# Toplevel.net
KiCad netlist of a schematic drawn in Altium Designer
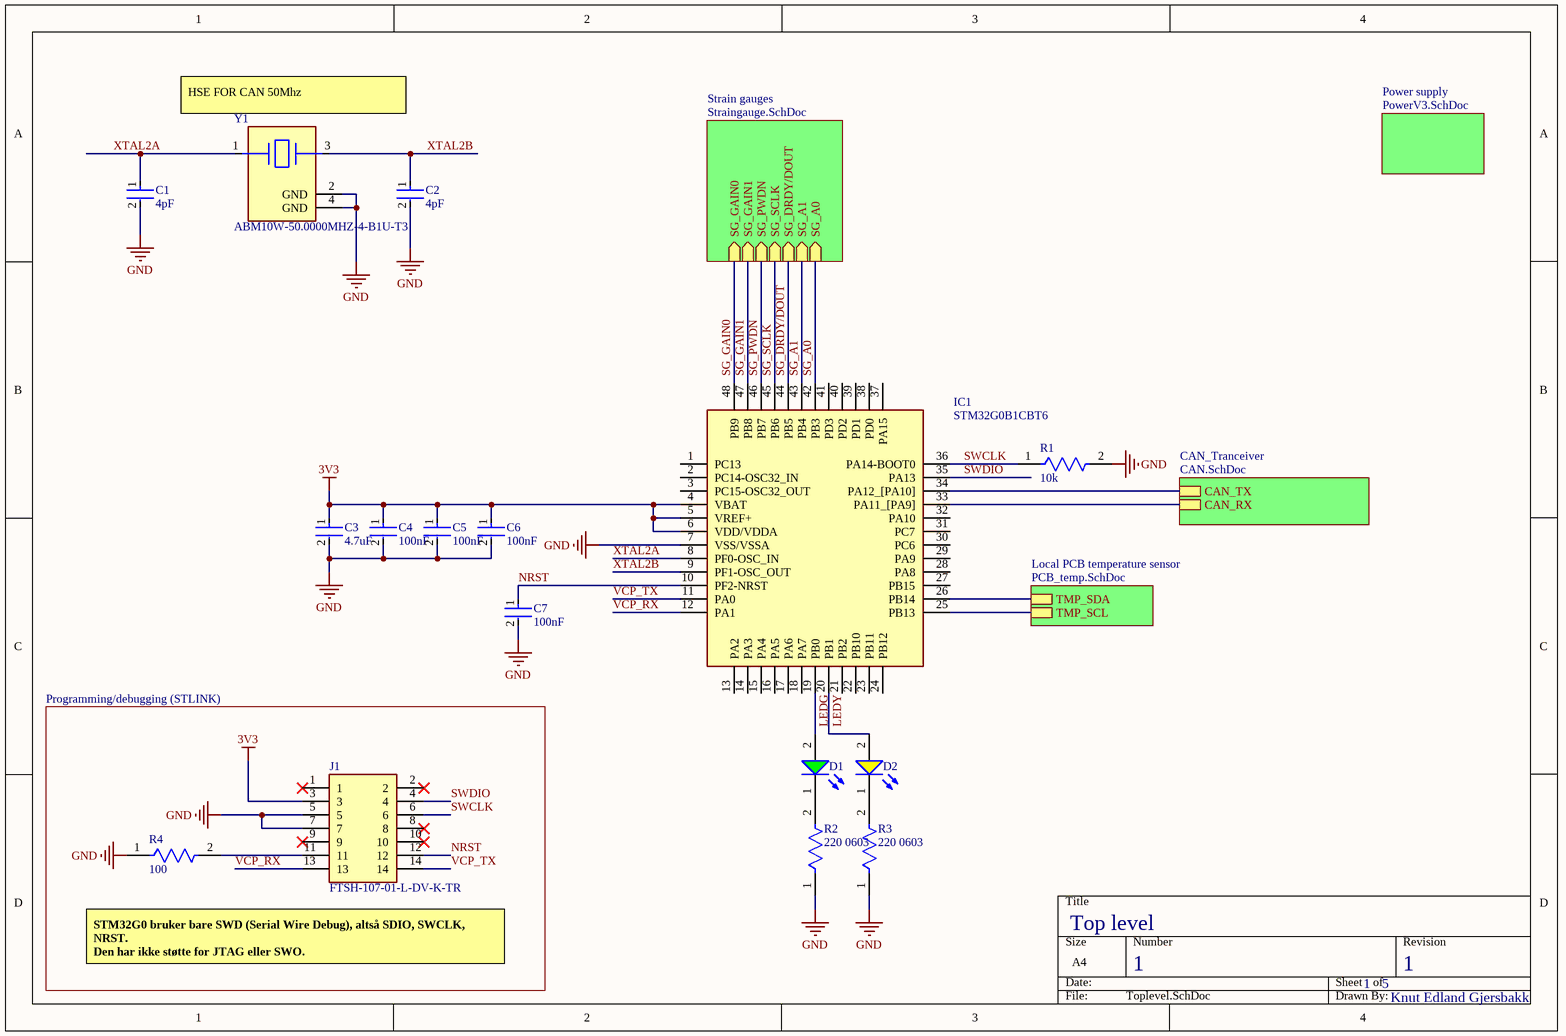
[diagram p0: Toplevel.SchDoc]

(export (version "E")
  (design (tool "Eeschema 10.0.6"))
  (components
    (comp (ref "C1")
      (value "4pF")
      (footprint "FP-GQM187-0_15-IPC_B")
      (description "GQM1875C2E4R0BB12D\r\nCeramic Capacitor 4pF ±0.1pF 250VDC C0G 0603 Paper T/R")
      (libsource (lib "Altium Content Vault") (part "02cd4be3c70576c341d710602a673aa"))
    )
    (comp (ref "C2")
      (value "4pF")
      (footprint "FP-GQM187-0_15-IPC_B")
      (description "GQM1875C2E4R0BB12D\r\nCeramic Capacitor 4pF ±0.1pF 250VDC C0G 0603 Paper T/R")
      (libsource (lib "Altium Content Vault") (part "02cd4be3c70576c341d710602a673aa"))
    )
    (comp (ref "C3")
      (value "4.7uF")
      (footprint "FP-GCM21B-0_15-IPC_A")
      (description "Ceramic Capacitor for Automotive 4.7uF ±10% 16VDC X7R 0805 Embossed T/R")
      (fields (field (name "TOLERANCE") "10%") (field (name "VOLTAGE") "16V"))
      (libsource (lib "Altium Content Vault") (part "02cd4be3c70576c341d710602a673aa"))
    )
    (comp (ref "C4")
      (value "100nF")
      (footprint "FP-CL10-IPC_A")
      (description "Cap Ceramic 100nF 16V X7R ±10% Pad SMD 0603 +125°C T/R")
      (fields (field (name "TOLERANCE") "10%"))
      (libsource (lib "Altium Content Vault") (part "b4654b650e69147ec39a6b967a45e02"))
    )
    (comp (ref "C5")
      (value "100nF")
      (footprint "FP-CL10-IPC_A")
      (description "Cap Ceramic 100nF 16V X7R ±10% Pad SMD 0603 +125°C T/R")
      (fields (field (name "TOLERANCE") "10%"))
      (libsource (lib "Altium Content Vault") (part "b4654b650e69147ec39a6b967a45e02"))
    )
    (comp (ref "C6")
      (value "100nF")
      (footprint "FP-CL10-IPC_A")
      (description "Cap Ceramic 100nF 16V X7R ±10% Pad SMD 0603 +125°C T/R")
      (fields (field (name "TOLERANCE") "10%"))
      (libsource (lib "Altium Content Vault") (part "b4654b650e69147ec39a6b967a45e02"))
    )
    (comp (ref "C7")
      (value "100nF")
      (footprint "FP-CL10-IPC_A")
      (description "Cap Ceramic 100nF 16V X7R ±10% Pad SMD 0603 +125°C T/R")
      (fields (field (name "TOLERANCE") "10%"))
      (libsource (lib "Altium Content Vault") (part "b4654b650e69147ec39a6b967a45e02"))
    )
    (comp (ref "D1")
      (value "150060GS55040")
      (footprint "WL-SMCD_0603")
      (description "150060GS55040 WL-SMCD SMT Mono-color Chip LED Diffused")
      (libsource (lib "Altium Content Vault") (part "LED_Green_2A-1K"))
    )
    (comp (ref "D2")
      (value "150060YS75020")
      (footprint "WL-SMCW_0603_150060xx75020")
      (description "WL-SMCW SMT Mono-Color Chip LED Waterclear super f")
      (libsource (lib "Altium Content Vault") (part "LED_Yellow_2A-1K"))
    )
    (comp (ref "IC1")
      (value "STM32G0B1CBT6")
      (footprint "SamacSys:QFP50P900X900X160-48N")
      (description "Integrated Circuit")
      (fields (field (name "MOUSER PART NUMBER") "511-STM32G0B1CBT6"))
      (libsource (lib "*") (part "STM32G0B1CBT6"))
    )
    (comp (ref "J1")
      (value "FTSH-107-01-L-DV-K-TR")
      (footprint "SamacSys:FTSH10701LDVKTR")
      (description "Connector")
      (fields (field (name "MOUSER PART NUMBER") "200-FTSH10701LDVKTR"))
      (libsource (lib "*") (part "FTSH-107-01-L-DV-K-TR"))
    )
    (comp (ref "R1")
      (value "10k")
      (footprint "FP-RT0603-IPC_C")
      (description "RES SMD 10K OHM 1% 1/10W 0603\r\nRT0603FRE0710KL")
      (fields
        (field (name "MANUFACTURER") "Yageo")
        (field (name "OCTOPART") "https://octopart.com/rt0603fre0710kl-yageo-40009243")
      )
      (libsource (lib "Altium Content Vault") (part "1029c3af85768c4190bb7ad29bc67b5"))
    )
    (comp (ref "R2")
      (value "220 0603")
      (footprint "FP-AF0603-IPC_C")
      (description "AF0603JR-07220RL Anti-Sulfurated Chip Resistors Automotive Grade 220Ω 5% 100ppm/°C 0603")
      (fields (field (name "TOLERANCE") "5%"))
      (libsource (lib "Altium Content Vault") (part "1029c3af85768c4190bb7ad29bc67b5"))
    )
    (comp (ref "R3")
      (value "220 0603")
      (footprint "FP-AF0603-IPC_C")
      (description "AF0603JR-07220RL Anti-Sulfurated Chip Resistors Automotive Grade 220Ω 5% 100ppm/°C 0603")
      (fields (field (name "TOLERANCE") "5%"))
      (libsource (lib "Altium Content Vault") (part "1029c3af85768c4190bb7ad29bc67b5"))
    )
    (comp (ref "R4")
      (value "100")
      (footprint "FP-RT0603-MFG")
      (description "RT0603 100Ω 0.1W 50 ppm/°C 1.00% RT0603FRE07100RL")
      (fields
        (field (name "OCTOPART") "https://octopart.com/rt0603fre10100rl-yageo-22252409")
        (field (name "TOLERANCE") "0.01")
      )
      (libsource (lib "Altium Content Vault") (part "1029c3af85768c4190bb7ad29bc67b5"))
    )
    (comp (ref "Y1")
      (value "ABM10W-50.0000MHZ-4-B1U-T3")
      (footprint "FP-ABM10W-MFG")
      (description "Crystal 50MHz ±10ppm 4pF SMD-4 2.5mm x 2mm")
      (libsource (lib "Altium Content Vault") (part "5d53a81b36bb19e40e9e80ec3e46f97"))
    )
  )
  (nets
    (net (code "1") (name "/CAN_RX") (class "Default")
      (node (ref "IC1") (pin "33") (pinfunction "PA11_[PA9]_33") (pintype "passive"))
    )
    (net (code "2") (name "/CAN_TX") (class "Default")
      (node (ref "IC1") (pin "34") (pinfunction "PA12_[PA10]_34") (pintype "passive"))
    )
    (net (code "3") (name "/LEDG") (class "Default")
      (node (ref "D1") (pin "2") (pinfunction "A_2") (pintype "passive"))
      (node (ref "IC1") (pin "19") (pinfunction "PB0_19") (pintype "passive"))
    )
    (net (code "4") (name "/LEDY") (class "Default")
      (node (ref "D2") (pin "2") (pinfunction "A_2") (pintype "passive"))
      (node (ref "IC1") (pin "20") (pinfunction "PB1_20") (pintype "passive"))
    )
    (net (code "5") (name "/NRST") (class "Default")
      (node (ref "C7") (pin "1") (pinfunction "1_1") (pintype "passive"))
      (node (ref "IC1") (pin "10") (pinfunction "PF2-NRST_10") (pintype "passive"))
      (node (ref "J1") (pin "12") (pinfunction "12_12") (pintype "passive"))
    )
    (net (code "6") (name "/SG_A0") (class "Default")
      (node (ref "IC1") (pin "42") (pinfunction "PB3_42") (pintype "passive"))
    )
    (net (code "7") (name "/SG_A1") (class "Default")
      (node (ref "IC1") (pin "43") (pinfunction "PB4_43") (pintype "passive"))
    )
    (net (code "8") (name "/SG_DRDY{slash}DOUT") (class "Default")
      (node (ref "IC1") (pin "44") (pinfunction "PB5_44") (pintype "passive"))
    )
    (net (code "9") (name "/SG_GAIN0") (class "Default")
      (node (ref "IC1") (pin "48") (pinfunction "PB9_48") (pintype "passive"))
    )
    (net (code "10") (name "/SG_GAIN1") (class "Default")
      (node (ref "IC1") (pin "47") (pinfunction "PB8_47") (pintype "passive"))
    )
    (net (code "11") (name "/SG_PWDN") (class "Default")
      (node (ref "IC1") (pin "46") (pinfunction "PB7_46") (pintype "passive"))
    )
    (net (code "12") (name "/SG_SCLK") (class "Default")
      (node (ref "IC1") (pin "45") (pinfunction "PB6_45") (pintype "passive"))
    )
    (net (code "13") (name "/SWCLK") (class "Default")
      (node (ref "IC1") (pin "36") (pinfunction "PA14-BOOT0_36") (pintype "passive"))
      (node (ref "J1") (pin "6") (pinfunction "6_6") (pintype "passive"))
      (node (ref "R1") (pin "1") (pinfunction "1_1") (pintype "passive"))
    )
    (net (code "14") (name "/SWDIO") (class "Default")
      (node (ref "IC1") (pin "35") (pinfunction "PA13_35") (pintype "passive"))
      (node (ref "J1") (pin "4") (pinfunction "4_4") (pintype "passive"))
    )
    (net (code "15") (name "/TMP_SCL") (class "Default")
      (node (ref "IC1") (pin "25") (pinfunction "PB13_25") (pintype "passive"))
    )
    (net (code "16") (name "/TMP_SDA") (class "Default")
      (node (ref "IC1") (pin "26") (pinfunction "PB14_26") (pintype "passive"))
    )
    (net (code "17") (name "/VCP_RX") (class "Default")
      (node (ref "IC1") (pin "12") (pinfunction "PA1_12") (pintype "passive"))
      (node (ref "J1") (pin "13") (pinfunction "13_13") (pintype "passive"))
    )
    (net (code "18") (name "/VCP_TX") (class "Default")
      (node (ref "IC1") (pin "11") (pinfunction "PA0_11") (pintype "passive"))
      (node (ref "J1") (pin "14") (pinfunction "14_14") (pintype "passive"))
    )
    (net (code "19") (name "/XTAL2A") (class "Default")
      (node (ref "C1") (pin "1") (pinfunction "1_1") (pintype "passive"))
      (node (ref "IC1") (pin "8") (pinfunction "PF0-OSC_IN_8") (pintype "passive"))
      (node (ref "Y1") (pin "1") (pinfunction "1_1") (pintype "passive"))
    )
    (net (code "20") (name "/XTAL2B") (class "Default")
      (node (ref "C2") (pin "1") (pinfunction "1_1") (pintype "passive"))
      (node (ref "IC1") (pin "9") (pinfunction "PF1-OSC_OUT_9") (pintype "passive"))
      (node (ref "Y1") (pin "3") (pinfunction "3_3") (pintype "passive"))
    )
    (net (code "21") (name "3V3") (class "Default")
      (node (ref "C3") (pin "1") (pinfunction "1_1") (pintype "passive"))
      (node (ref "C4") (pin "1") (pinfunction "1_1") (pintype "passive"))
      (node (ref "C5") (pin "1") (pinfunction "1_1") (pintype "passive"))
      (node (ref "C6") (pin "1") (pinfunction "1_1") (pintype "passive"))
      (node (ref "IC1") (pin "4") (pinfunction "VBAT_4") (pintype "passive"))
      (node (ref "IC1") (pin "5") (pinfunction "VREF+_5") (pintype "passive"))
      (node (ref "IC1") (pin "6") (pinfunction "VDD/VDDA_6") (pintype "passive"))
      (node (ref "J1") (pin "3") (pinfunction "3_3") (pintype "passive"))
    )
    (net (code "22") (name "GND") (class "Default")
      (node (ref "C1") (pin "2") (pinfunction "2_2") (pintype "passive"))
      (node (ref "C2") (pin "2") (pinfunction "2_2") (pintype "passive"))
      (node (ref "C3") (pin "2") (pinfunction "2_2") (pintype "passive"))
      (node (ref "C4") (pin "2") (pinfunction "2_2") (pintype "passive"))
      (node (ref "C5") (pin "2") (pinfunction "2_2") (pintype "passive"))
      (node (ref "C6") (pin "2") (pinfunction "2_2") (pintype "passive"))
      (node (ref "C7") (pin "2") (pinfunction "2_2") (pintype "passive"))
      (node (ref "IC1") (pin "7") (pinfunction "VSS/VSSA_7") (pintype "passive"))
      (node (ref "J1") (pin "5") (pinfunction "5_5") (pintype "passive"))
      (node (ref "J1") (pin "7") (pinfunction "7_7") (pintype "passive"))
      (node (ref "R1") (pin "2") (pinfunction "2_2") (pintype "passive"))
      (node (ref "R2") (pin "1") (pinfunction "1_1") (pintype "passive"))
      (node (ref "R3") (pin "1") (pinfunction "1_1") (pintype "passive"))
      (node (ref "R4") (pin "1") (pinfunction "1_1") (pintype "passive"))
      (node (ref "Y1") (pin "2") (pinfunction "GND_2") (pintype "power_in"))
      (node (ref "Y1") (pin "4") (pinfunction "GND_4") (pintype "power_in"))
    )
    (net (code "23") (name "Net-(D1-K)") (class "Default")
      (node (ref "D1") (pin "1") (pinfunction "K_1") (pintype "passive"))
      (node (ref "R2") (pin "2") (pinfunction "2_2") (pintype "passive"))
    )
    (net (code "24") (name "Net-(D2-K)") (class "Default")
      (node (ref "D2") (pin "1") (pinfunction "K_1") (pintype "passive"))
      (node (ref "R3") (pin "2") (pinfunction "2_2") (pintype "passive"))
    )
    (net (code "25") (name "Net-(J1-Pad11)") (class "Default")
      (node (ref "J1") (pin "11") (pinfunction "11_11") (pintype "passive"))
      (node (ref "R4") (pin "2") (pinfunction "2_2") (pintype "passive"))
    )
    (net (code "26") (name "unconnected-(IC1-PA2-Pad13)") (class "Default")
      (node (ref "IC1") (pin "13") (pinfunction "PA2_13") (pintype "passive"))
    )
    (net (code "27") (name "unconnected-(IC1-PA3-Pad14)") (class "Default")
      (node (ref "IC1") (pin "14") (pinfunction "PA3_14") (pintype "passive"))
    )
    (net (code "28") (name "unconnected-(IC1-PA4-Pad15)") (class "Default")
      (node (ref "IC1") (pin "15") (pinfunction "PA4_15") (pintype "passive"))
    )
    (net (code "29") (name "unconnected-(IC1-PA5-Pad16)") (class "Default")
      (node (ref "IC1") (pin "16") (pinfunction "PA5_16") (pintype "passive"))
    )
    (net (code "30") (name "unconnected-(IC1-PA6-Pad17)") (class "Default")
      (node (ref "IC1") (pin "17") (pinfunction "PA6_17") (pintype "passive"))
    )
    (net (code "31") (name "unconnected-(IC1-PA7-Pad18)") (class "Default")
      (node (ref "IC1") (pin "18") (pinfunction "PA7_18") (pintype "passive"))
    )
    (net (code "32") (name "unconnected-(IC1-PA8-Pad28)") (class "Default")
      (node (ref "IC1") (pin "28") (pinfunction "PA8_28") (pintype "passive"))
    )
    (net (code "33") (name "unconnected-(IC1-PA9-Pad29)") (class "Default")
      (node (ref "IC1") (pin "29") (pinfunction "PA9_29") (pintype "passive"))
    )
    (net (code "34") (name "unconnected-(IC1-PA10-Pad32)") (class "Default")
      (node (ref "IC1") (pin "32") (pinfunction "PA10_32") (pintype "passive"))
    )
    (net (code "35") (name "unconnected-(IC1-PA15-Pad37)") (class "Default")
      (node (ref "IC1") (pin "37") (pinfunction "PA15_37") (pintype "passive"))
    )
    (net (code "36") (name "unconnected-(IC1-PB2-Pad21)") (class "Default")
      (node (ref "IC1") (pin "21") (pinfunction "PB2_21") (pintype "passive"))
    )
    (net (code "37") (name "unconnected-(IC1-PB10-Pad22)") (class "Default")
      (node (ref "IC1") (pin "22") (pinfunction "PB10_22") (pintype "passive"))
    )
    (net (code "38") (name "unconnected-(IC1-PB11-Pad23)") (class "Default")
      (node (ref "IC1") (pin "23") (pinfunction "PB11_23") (pintype "passive"))
    )
    (net (code "39") (name "unconnected-(IC1-PB12-Pad24)") (class "Default")
      (node (ref "IC1") (pin "24") (pinfunction "PB12_24") (pintype "passive"))
    )
    (net (code "40") (name "unconnected-(IC1-PB15-Pad27)") (class "Default")
      (node (ref "IC1") (pin "27") (pinfunction "PB15_27") (pintype "passive"))
    )
    (net (code "41") (name "unconnected-(IC1-PC6-Pad30)") (class "Default")
      (node (ref "IC1") (pin "30") (pinfunction "PC6_30") (pintype "passive"))
    )
    (net (code "42") (name "unconnected-(IC1-PC7-Pad31)") (class "Default")
      (node (ref "IC1") (pin "31") (pinfunction "PC7_31") (pintype "passive"))
    )
    (net (code "43") (name "unconnected-(IC1-PC13-Pad1)") (class "Default")
      (node (ref "IC1") (pin "1") (pinfunction "PC13_1") (pintype "passive"))
    )
    (net (code "44") (name "unconnected-(IC1-PC14-OSC32_IN-Pad2)") (class "Default")
      (node (ref "IC1") (pin "2") (pinfunction "PC14-OSC32_IN_2") (pintype "passive"))
    )
    (net (code "45") (name "unconnected-(IC1-PC15-OSC32_OUT-Pad3)") (class "Default")
      (node (ref "IC1") (pin "3") (pinfunction "PC15-OSC32_OUT_3") (pintype "passive"))
    )
    (net (code "46") (name "unconnected-(IC1-PD0-Pad38)") (class "Default")
      (node (ref "IC1") (pin "38") (pinfunction "PD0_38") (pintype "passive"))
    )
    (net (code "47") (name "unconnected-(IC1-PD1-Pad39)") (class "Default")
      (node (ref "IC1") (pin "39") (pinfunction "PD1_39") (pintype "passive"))
    )
    (net (code "48") (name "unconnected-(IC1-PD2-Pad40)") (class "Default")
      (node (ref "IC1") (pin "40") (pinfunction "PD2_40") (pintype "passive"))
    )
    (net (code "49") (name "unconnected-(IC1-PD3-Pad41)") (class "Default")
      (node (ref "IC1") (pin "41") (pinfunction "PD3_41") (pintype "passive"))
    )
    (net (code "50") (name "unconnected-(J1-Pad1)") (class "Default")
      (node (ref "J1") (pin "1") (pinfunction "1_1") (pintype "passive+no_connect"))
    )
    (net (code "51") (name "unconnected-(J1-Pad2)") (class "Default")
      (node (ref "J1") (pin "2") (pinfunction "2_2") (pintype "passive+no_connect"))
    )
    (net (code "52") (name "unconnected-(J1-Pad8)") (class "Default")
      (node (ref "J1") (pin "8") (pinfunction "8_8") (pintype "passive+no_connect"))
    )
    (net (code "53") (name "unconnected-(J1-Pad9)") (class "Default")
      (node (ref "J1") (pin "9") (pinfunction "9_9") (pintype "passive+no_connect"))
    )
    (net (code "54") (name "unconnected-(J1-Pad10)") (class "Default")
      (node (ref "J1") (pin "10") (pinfunction "10_10") (pintype "passive+no_connect"))
    )
  )
)
